# Microcontroller.net
KiCad netlist of a schematic drawn in Altium Designer
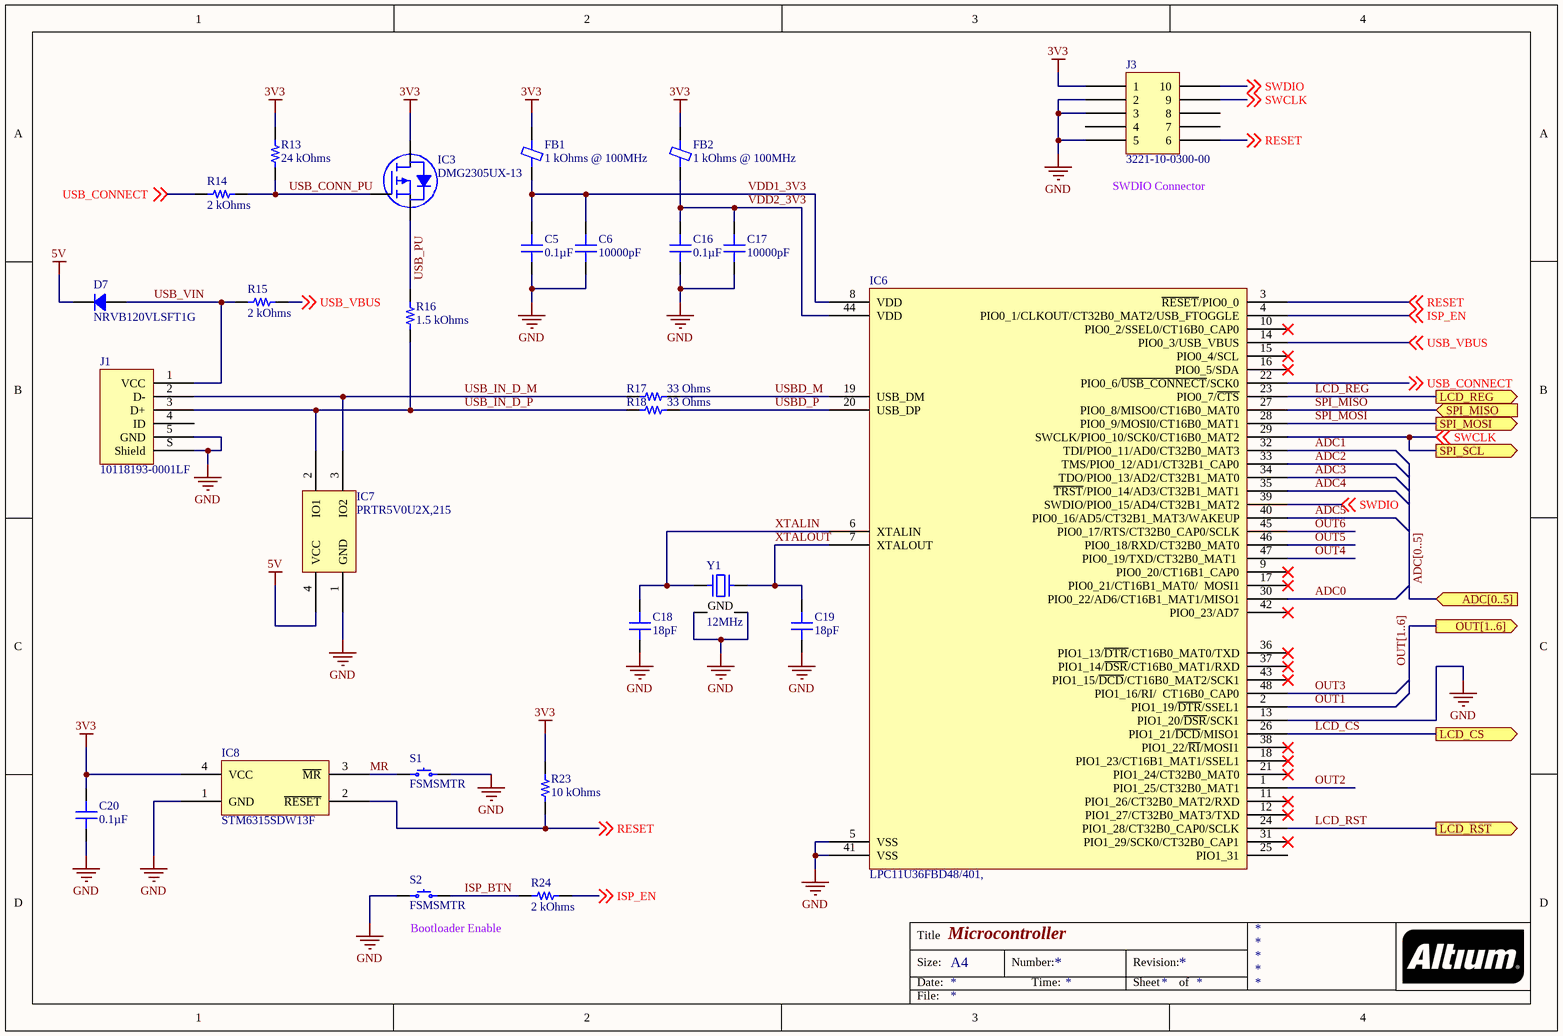
[diagram p0: Microcontroller.SchDoc]

(export (version "E")
  (design (tool "Eeschema 10.0.6"))
  (components
    (comp (ref "C5")
      (value "0.1µF")
      (footprint "CAP 0603_1608")
      (description "CAP CER 0.1UF 16V X7R 0603")
      (fields (field (name "PART NUMBER") "CS0603KRX7R7BB104") (field (name "MANUFACTURER") "Yageo"))
      (libsource (lib "Celestial Altium Library - altium_library") (part "Capacitor"))
    )
    (comp (ref "C6")
      (value "10000pF")
      (footprint "CAP 0603_1608")
      (description "CAP CER 10000PF 50V X7R 0603")
      (fields (field (name "PART NUMBER") "AC0603KPX7R9BB103") (field (name "MANUFACTURER") "Yageo"))
      (libsource (lib "Celestial Altium Library - altium_library") (part "Capacitor"))
    )
    (comp (ref "C16")
      (value "0.1µF")
      (footprint "CAP 0603_1608")
      (description "CAP CER 0.1UF 16V X7R 0603")
      (fields (field (name "PART NUMBER") "CS0603KRX7R7BB104") (field (name "MANUFACTURER") "Yageo"))
      (libsource (lib "Celestial Altium Library - altium_library") (part "Capacitor"))
    )
    (comp (ref "C17")
      (value "10000pF")
      (footprint "CAP 0603_1608")
      (description "CAP CER 10000PF 50V X7R 0603")
      (fields (field (name "PART NUMBER") "AC0603KPX7R9BB103") (field (name "MANUFACTURER") "Yageo"))
      (libsource (lib "Celestial Altium Library - altium_library") (part "Capacitor"))
    )
    (comp (ref "C18")
      (value "18pF")
      (footprint "CAP 0603_1608")
      (description "CAP CER 18PF 50V C0G/NP0 0603")
      (fields (field (name "PART NUMBER") "C0603C180K5GACTU") (field (name "MANUFACTURER") "KEMET"))
      (libsource (lib "Celestial Altium Library - altium_library") (part "Capacitor"))
    )
    (comp (ref "C19")
      (value "18pF")
      (footprint "CAP 0603_1608")
      (description "CAP CER 18PF 50V C0G/NP0 0603")
      (fields (field (name "PART NUMBER") "C0603C180K5GACTU") (field (name "MANUFACTURER") "KEMET"))
      (libsource (lib "Celestial Altium Library - altium_library") (part "Capacitor"))
    )
    (comp (ref "C20")
      (value "0.1µF")
      (footprint "CAP 0603_1608")
      (description "CAP CER 0.1UF 16V X7R 0603")
      (fields (field (name "PART NUMBER") "CS0603KRX7R7BB104") (field (name "MANUFACTURER") "Yageo"))
      (libsource (lib "Celestial Altium Library - altium_library") (part "Capacitor"))
    )
    (comp (ref "D7")
      (value "NRVB120VLSFT1G")
      (footprint "SOD123F")
      (description "DIODE SCHOTTKY 20V 1A SOD123")
      (fields (field (name "MANUFACTURER") "ON Semiconductor"))
      (libsource (lib "Celestial Altium Library - altium_library") (part "Diode"))
    )
    (comp (ref "FB1")
      (value "1 kOhms @ 100MHz")
      (footprint "FER 0603_1608")
      (description "FERRITE BEAD,HIGH CURRENT, 0603")
      (fields (field (name "PART NUMBER") "FBTH1608HE102-T") (field (name "MANUFACTURER") "Taiyo Yuden"))
      (libsource (lib "Celestial Altium Library - altium_library") (part "Ferrite Chip"))
    )
    (comp (ref "FB2")
      (value "1 kOhms @ 100MHz")
      (footprint "FER 0603_1608")
      (description "FERRITE BEAD,HIGH CURRENT, 0603")
      (fields (field (name "PART NUMBER") "FBTH1608HE102-T") (field (name "MANUFACTURER") "Taiyo Yuden"))
      (libsource (lib "Celestial Altium Library - altium_library") (part "Ferrite Chip"))
    )
    (comp (ref "IC3")
      (value "DMG2305UX-13")
      (footprint "DIODES SOT-23-3")
      (description "MOSFET P-CH 20V 4.2A SOT23")
      (fields (field (name "MANUFACTURER") "Diodes Incorporated"))
      (libsource (lib "Celestial Altium Library - altium_library") (part "DIODES MOSFET P-CH SOT-23-3"))
    )
    (comp (ref "IC6")
      (value "LPC11U36FBD48/401,")
      (footprint "NXP LQFP-48 7X7MM")
      (description "IC MCU 32BIT 96KB FLASH 48LQFP")
      (fields (field (name "MANUFACTURER") "NXP USA Inc."))
      (libsource (lib "Celestial Altium Library - altium_library") (part "NXP LPC11U3X LQFP48"))
    )
    (comp (ref "IC7")
      (value "PRTR5V0U2X,215")
      (footprint "SOT143B")
      (description "TVS DIODE 5.5V SOT143B")
      (fields (field (name "MANUFACTURER") "Nexperia USA Inc."))
      (libsource (lib "Celestial Altium Library - altium_library") (part "NXP PRTR5V0U2X"))
    )
    (comp (ref "IC8")
      (value "STM6315SDW13F")
      (footprint "ST SOT-143-4")
      (description "IC SUPERVISOR 1 CHANNEL SOT143-4")
      (fields (field (name "MANUFACTURER") "STMicroelectronics"))
      (libsource (lib "Celestial Altium Library - altium_library") (part "ST STM3615"))
    )
    (comp (ref "J1")
      (value "10118193-0001LF")
      (footprint "FCI USB 10118193-0001LF")
      (description "CONN RCPT USB2.0 MICRO B SMD R/A")
      (fields (field (name "MANUFACTURER") "Amphenol ICC (FCI)"))
      (libsource (lib "Celestial Altium Library - altium_library") (part "USB 2.0 Type B Micro"))
    )
    (comp (ref "J3")
      (value "3221-10-0300-00")
      (footprint "CNC TECH 3221-10-0300-00")
      (description "CONN HEADER SMD 10POS 1.27MM")
      (fields (field (name "MANUFACTURER") "CNC Tech"))
      (libsource (lib "Celestial Altium Library - altium_library") (part "2x5 Pin"))
    )
    (comp (ref "R13")
      (value "24 kOhms")
      (footprint "RES 0603_1608")
      (description "RES SMD 24K OHM 1% 1/10W 0603")
      (fields
        (field (name "PART NUMBER") "ERJ-3EKF2402V")
        (field (name "MANUFACTURER") "Panasonic Electronic Components")
      )
      (libsource (lib "Celestial Altium Library - altium_library") (part "Resistor"))
    )
    (comp (ref "R14")
      (value "2 kOhms")
      (footprint "RES 0603_1608")
      (description "RES SMD 2K OHM 1% 1/10W 0603")
      (fields
        (field (name "PART NUMBER") "ERJ-3EKF2001V")
        (field (name "MANUFACTURER") "Panasonic Electronic Components")
      )
      (libsource (lib "Celestial Altium Library - altium_library") (part "Resistor"))
    )
    (comp (ref "R15")
      (value "2 kOhms")
      (footprint "RES 0603_1608")
      (description "RES SMD 2K OHM 5% 1/4W 0603")
      (fields
        (field (name "PART NUMBER") "ERJ-PA3J202V")
        (field (name "MANUFACTURER") "Panasonic Electronic Components")
      )
      (libsource (lib "Celestial Altium Library - altium_library") (part "Resistor"))
    )
    (comp (ref "R16")
      (value "1.5 kOhms")
      (footprint "RES 0603_1608")
      (description "RES SMD 1.5K OHM 1% 1/10W 0603")
      (fields
        (field (name "PART NUMBER") "ERJ-3EKF1501V")
        (field (name "MANUFACTURER") "Panasonic Electronic Components")
      )
      (libsource (lib "Celestial Altium Library - altium_library") (part "Resistor"))
    )
    (comp (ref "R17")
      (value "33 Ohms")
      (footprint "RES 0603_1608")
      (description "RES SMD 33 OHM 1% 1/10W 0603")
      (fields
        (field (name "PART NUMBER") "ERJ-3EKF33R0V")
        (field (name "MANUFACTURER") "Panasonic Electronic Components")
      )
      (libsource (lib "Celestial Altium Library - altium_library") (part "Resistor"))
    )
    (comp (ref "R18")
      (value "33 Ohms")
      (footprint "RES 0603_1608")
      (description "RES SMD 33 OHM 1% 1/10W 0603")
      (fields
        (field (name "PART NUMBER") "ERJ-3EKF33R0V")
        (field (name "MANUFACTURER") "Panasonic Electronic Components")
      )
      (libsource (lib "Celestial Altium Library - altium_library") (part "Resistor"))
    )
    (comp (ref "R23")
      (value "10 kOhms")
      (footprint "RES 0603_1608")
      (description "RES SMD 10K OHM 1% 1/10W 0603")
      (fields
        (field (name "PART NUMBER") "ERJ-3EKF1002V")
        (field (name "MANUFACTURER") "Panasonic Electronic Components")
      )
      (libsource (lib "Celestial Altium Library - altium_library") (part "Resistor"))
    )
    (comp (ref "R24")
      (value "2 kOhms")
      (footprint "RES 0603_1608")
      (description "RES SMD 2K OHM 5% 1/4W 0603")
      (fields
        (field (name "PART NUMBER") "ERJ-PA3J202V")
        (field (name "MANUFACTURER") "Panasonic Electronic Components")
      )
      (libsource (lib "Celestial Altium Library - altium_library") (part "Resistor"))
    )
    (comp (ref "S1")
      (value "FSMSMTR")
      (footprint "TE FSMSMTR")
      (description "SWITCH TACTILE SPST-NO 0.05A 24V")
      (fields (field (name "MANUFACTURER") "TE Connectivity ALCOSWITCH Switches"))
      (libsource (lib "Celestial Altium Library - altium_library") (part "SPST-NO 2 PIN"))
    )
    (comp (ref "S2")
      (value "FSMSMTR")
      (footprint "TE FSMSMTR")
      (description "SWITCH TACTILE SPST-NO 0.05A 24V")
      (fields (field (name "MANUFACTURER") "TE Connectivity ALCOSWITCH Switches"))
      (libsource (lib "Celestial Altium Library - altium_library") (part "SPST-NO 2 PIN"))
    )
    (comp (ref "Y1")
      (value "12MHz")
      (footprint "ABRACON ABM8G")
      (description "IOT 12MHZ 10PF XTAL")
      (fields
        (field (name "PART NUMBER") "ABM8G-106-12.000MHZ-T")
        (field (name "MANUFACTURER") "Abracon LLC")
      )
      (libsource (lib "Celestial Altium Library - altium_library") (part "Abracon Crystal ABM8G"))
    )
  )
  (nets
    (net (code "1") (name "/ADC0") (class "Default")
      (node (ref "IC6") (pin "30") (pinfunction "PIO0_22/AD6/CT16B1_MAT1/MISO1_30") (pintype "passive"))
    )
    (net (code "2") (name "/ADC1") (class "Default")
      (node (ref "IC6") (pin "32") (pinfunction "TDI/PIO0_11/AD0/CT32B0_MAT3_32") (pintype "passive"))
    )
    (net (code "3") (name "/ADC2") (class "Default")
      (node (ref "IC6") (pin "33") (pinfunction "TMS/PIO0_12/AD1/CT32B1_CAP0_33") (pintype "passive"))
    )
    (net (code "4") (name "/ADC3") (class "Default")
      (node (ref "IC6") (pin "34") (pinfunction "TDO/PIO0_13/AD2/CT32B1_MAT0_34") (pintype "passive"))
    )
    (net (code "5") (name "/ADC4") (class "Default")
      (node (ref "IC6") (pin "35") (pinfunction "~{TRST}/PIO0_14/AD3/CT32B1_MAT1_35") (pintype "passive"))
    )
    (net (code "6") (name "/ADC5") (class "Default")
      (node (ref "IC6") (pin "40") (pinfunction "PIO0_16/AD5/CT32B1_MAT3/WAKEUP_40") (pintype "passive"))
    )
    (net (code "8") (name "/ISP_BTN") (class "Default")
      (node (ref "R24") (pin "1") (pinfunction "1_1") (pintype "passive"))
      (node (ref "S2") (pin "2") (pinfunction "2_2") (pintype "passive"))
    )
    (net (code "9") (name "/LCD_CS") (class "Default")
      (node (ref "IC6") (pin "26") (pinfunction "PIO1_21/~{DCD}/MISO1_26") (pintype "passive"))
    )
    (net (code "10") (name "/LCD_REG") (class "Default")
      (node (ref "IC6") (pin "23") (pinfunction "PIO0_7/~{CTS}_23") (pintype "passive"))
    )
    (net (code "11") (name "/LCD_RST") (class "Default")
      (node (ref "IC6") (pin "24") (pinfunction "PIO1_28/CT32B0_CAP0/SCLK_24") (pintype "passive"))
    )
    (net (code "12") (name "/MR") (class "Default")
      (node (ref "IC8") (pin "3") (pinfunction "~{MR}_3") (pintype "passive"))
      (node (ref "S1") (pin "1") (pinfunction "1_1") (pintype "passive"))
    )
    (net (code "13") (name "/OUT1") (class "Default")
      (node (ref "IC6") (pin "2") (pinfunction "PIO1_19/~{DTR}/SSEL1_2") (pintype "passive"))
    )
    (net (code "14") (name "/OUT2") (class "Default")
      (node (ref "IC6") (pin "1") (pinfunction "PIO1_25/CT32B0_MAT1_1") (pintype "passive"))
    )
    (net (code "15") (name "/OUT3") (class "Default")
      (node (ref "IC6") (pin "48") (pinfunction "PIO1_16/RI/__CT16B0_CAP0_48") (pintype "passive"))
    )
    (net (code "16") (name "/OUT4") (class "Default")
      (node (ref "IC6") (pin "47") (pinfunction "PIO0_19/TXD/CT32B0_MAT1_47") (pintype "passive"))
    )
    (net (code "17") (name "/OUT5") (class "Default")
      (node (ref "IC6") (pin "46") (pinfunction "PIO0_18/RXD/CT32B0_MAT0_46") (pintype "passive"))
    )
    (net (code "18") (name "/OUT6") (class "Default")
      (node (ref "IC6") (pin "45") (pinfunction "PIO0_17/RTS/CT32B0_CAP0/SCLK_45") (pintype "passive"))
    )
    (net (code "20") (name "/SPI_MISO") (class "Default")
      (node (ref "IC6") (pin "27") (pinfunction "PIO0_8/MISO0/CT16B0_MAT0_27") (pintype "passive"))
    )
    (net (code "21") (name "/SPI_MOSI") (class "Default")
      (node (ref "IC6") (pin "28") (pinfunction "PIO0_9/MOSI0/CT16B0_MAT1_28") (pintype "passive"))
    )
    (net (code "22") (name "/USBD_M") (class "Default")
      (node (ref "IC6") (pin "19") (pinfunction "USB_DM_19") (pintype "passive"))
      (node (ref "R17") (pin "2") (pinfunction "2_2") (pintype "passive"))
    )
    (net (code "23") (name "/USBD_P") (class "Default")
      (node (ref "IC6") (pin "20") (pinfunction "USB_DP_20") (pintype "passive"))
      (node (ref "R18") (pin "2") (pinfunction "2_2") (pintype "passive"))
    )
    (net (code "24") (name "/USB_CONN_PU") (class "Default")
      (node (ref "IC3") (pin "1") (pinfunction "G_1") (pintype "passive"))
      (node (ref "R13") (pin "1") (pinfunction "1_1") (pintype "passive"))
      (node (ref "R14") (pin "2") (pinfunction "2_2") (pintype "passive"))
    )
    (net (code "25") (name "/USB_IN_D_M") (class "Default")
      (node (ref "IC7") (pin "3") (pinfunction "IO2_3") (pintype "passive"))
      (node (ref "J1") (pin "2") (pinfunction "D-_2") (pintype "passive"))
      (node (ref "R17") (pin "1") (pinfunction "1_1") (pintype "passive"))
    )
    (net (code "26") (name "/USB_IN_D_P") (class "Default")
      (node (ref "IC7") (pin "2") (pinfunction "IO1_2") (pintype "passive"))
      (node (ref "J1") (pin "3") (pinfunction "D+_3") (pintype "passive"))
      (node (ref "R16") (pin "1") (pinfunction "1_1") (pintype "passive"))
      (node (ref "R18") (pin "1") (pinfunction "1_1") (pintype "passive"))
    )
    (net (code "27") (name "/USB_PU") (class "Default")
      (node (ref "IC3") (pin "2") (pinfunction "S_2") (pintype "passive"))
      (node (ref "R16") (pin "2") (pinfunction "2_2") (pintype "passive"))
    )
    (net (code "28") (name "/USB_VIN") (class "Default")
      (node (ref "D7") (pin "1") (pinfunction "1_1") (pintype "passive"))
      (node (ref "J1") (pin "1") (pinfunction "VCC_1") (pintype "passive"))
      (node (ref "R15") (pin "1") (pinfunction "1_1") (pintype "passive"))
    )
    (net (code "29") (name "/VDD1_3V3") (class "Default")
      (node (ref "C5") (pin "2") (pinfunction "2_2") (pintype "passive"))
      (node (ref "C6") (pin "2") (pinfunction "2_2") (pintype "passive"))
      (node (ref "FB1") (pin "1") (pinfunction "1_1") (pintype "passive"))
      (node (ref "IC6") (pin "8") (pinfunction "VDD_8") (pintype "passive"))
    )
    (net (code "30") (name "/VDD2_3V3") (class "Default")
      (node (ref "C16") (pin "2") (pinfunction "2_2") (pintype "passive"))
      (node (ref "C17") (pin "2") (pinfunction "2_2") (pintype "passive"))
      (node (ref "FB2") (pin "1") (pinfunction "1_1") (pintype "passive"))
      (node (ref "IC6") (pin "44") (pinfunction "VDD_44") (pintype "passive"))
    )
    (net (code "31") (name "/XTALIN") (class "Default")
      (node (ref "C18") (pin "2") (pinfunction "2_2") (pintype "passive"))
      (node (ref "IC6") (pin "6") (pinfunction "XTALIN_6") (pintype "passive"))
      (node (ref "Y1") (pin "1") (pinfunction "1_1") (pintype "passive"))
    )
    (net (code "32") (name "/XTALOUT") (class "Default")
      (node (ref "C19") (pin "2") (pinfunction "2_2") (pintype "passive"))
      (node (ref "IC6") (pin "7") (pinfunction "XTALOUT_7") (pintype "passive"))
      (node (ref "Y1") (pin "3") (pinfunction "3_3") (pintype "passive"))
    )
    (net (code "33") (name "3V3") (class "Default")
      (node (ref "C20") (pin "2") (pinfunction "2_2") (pintype "passive"))
      (node (ref "FB1") (pin "2") (pinfunction "2_2") (pintype "passive"))
      (node (ref "FB2") (pin "2") (pinfunction "2_2") (pintype "passive"))
      (node (ref "IC3") (pin "3") (pinfunction "D_3") (pintype "passive"))
      (node (ref "IC8") (pin "4") (pinfunction "VCC_4") (pintype "passive"))
      (node (ref "J3") (pin "1") (pinfunction "1_1") (pintype "passive"))
      (node (ref "R13") (pin "2") (pinfunction "2_2") (pintype "passive"))
      (node (ref "R23") (pin "2") (pinfunction "2_2") (pintype "passive"))
    )
    (net (code "34") (name "5V") (class "Default")
      (node (ref "D7") (pin "2") (pinfunction "2_2") (pintype "passive"))
      (node (ref "IC7") (pin "4") (pinfunction "VCC_4") (pintype "passive"))
    )
    (net (code "35") (name "GND") (class "Default")
      (node (ref "C16") (pin "1") (pinfunction "1_1") (pintype "passive"))
      (node (ref "C17") (pin "1") (pinfunction "1_1") (pintype "passive"))
      (node (ref "C18") (pin "1") (pinfunction "1_1") (pintype "passive"))
      (node (ref "C19") (pin "1") (pinfunction "1_1") (pintype "passive"))
      (node (ref "C20") (pin "1") (pinfunction "1_1") (pintype "passive"))
      (node (ref "C5") (pin "1") (pinfunction "1_1") (pintype "passive"))
      (node (ref "C6") (pin "1") (pinfunction "1_1") (pintype "passive"))
      (node (ref "IC6") (pin "13") (pinfunction "PIO1_20/~{DSR}/SCK1_13") (pintype "passive"))
      (node (ref "IC6") (pin "41") (pinfunction "VSS_41") (pintype "passive"))
      (node (ref "IC6") (pin "5") (pinfunction "VSS_5") (pintype "passive"))
      (node (ref "IC7") (pin "1") (pinfunction "GND_1") (pintype "passive"))
      (node (ref "IC8") (pin "1") (pinfunction "GND_1") (pintype "passive"))
      (node (ref "J1") (pin "5") (pinfunction "GND_5") (pintype "passive"))
      (node (ref "J1") (pin "S") (pinfunction "Shield_S") (pintype "passive"))
      (node (ref "J3") (pin "2") (pinfunction "2_2") (pintype "passive"))
      (node (ref "J3") (pin "3") (pinfunction "3_3") (pintype "passive"))
      (node (ref "J3") (pin "5") (pinfunction "5_5") (pintype "passive"))
      (node (ref "S1") (pin "2") (pinfunction "2_2") (pintype "passive"))
      (node (ref "S2") (pin "1") (pinfunction "1_1") (pintype "passive"))
      (node (ref "Y1") (pin "2") (pinfunction "GND_2") (pintype "passive"))
      (node (ref "Y1") (pin "4") (pinfunction "GND_4") (pintype "passive"))
    )
    (net (code "36") (name "ISP_EN") (class "Default")
      (node (ref "IC6") (pin "4") (pinfunction "PIO0_1/CLKOUT/CT32B0_MAT2/USB_FTOGGLE_4") (pintype "passive"))
      (node (ref "R24") (pin "2") (pinfunction "2_2") (pintype "passive"))
    )
    (net (code "37") (name "RESET") (class "Default")
      (node (ref "IC6") (pin "3") (pinfunction "~{RESET}/PIO0_0_3") (pintype "passive"))
      (node (ref "IC8") (pin "2") (pinfunction "~{RESET}_2") (pintype "passive"))
      (node (ref "J3") (pin "6") (pinfunction "6_6") (pintype "passive"))
      (node (ref "R23") (pin "1") (pinfunction "1_1") (pintype "passive"))
    )
    (net (code "38") (name "SWCLK") (class "Default")
      (node (ref "IC6") (pin "29") (pinfunction "SWCLK/PIO0_10/SCK0/CT16B0_MAT2_29") (pintype "passive"))
      (node (ref "J3") (pin "9") (pinfunction "9_9") (pintype "passive"))
    )
    (net (code "39") (name "SWDIO") (class "Default")
      (node (ref "IC6") (pin "39") (pinfunction "SWDIO/PIO0_15/AD4/CT32B1_MAT2_39") (pintype "passive"))
      (node (ref "J3") (pin "10") (pinfunction "10_10") (pintype "passive"))
    )
    (net (code "40") (name "USB_CONNECT") (class "Default")
      (node (ref "IC6") (pin "22") (pinfunction "PIO0_6/~{USB_CONNECT}/SCK0_22") (pintype "passive"))
      (node (ref "R14") (pin "1") (pinfunction "1_1") (pintype "passive"))
    )
    (net (code "41") (name "USB_VBUS") (class "Default")
      (node (ref "IC6") (pin "14") (pinfunction "PIO0_3/USB_VBUS_14") (pintype "passive"))
      (node (ref "R15") (pin "2") (pinfunction "2_2") (pintype "passive"))
    )
    (net (code "42") (name "unconnected-(IC6-PIO0_2{slash}SSEL0{slash}CT16B0_CAP0-Pad10)") (class "Default")
      (node (ref "IC6") (pin "10") (pinfunction "PIO0_2/SSEL0/CT16B0_CAP0_10") (pintype "passive+no_connect"))
    )
    (net (code "43") (name "unconnected-(IC6-PIO0_4{slash}SCL-Pad15)") (class "Default")
      (node (ref "IC6") (pin "15") (pinfunction "PIO0_4/SCL_15") (pintype "passive+no_connect"))
    )
    (net (code "44") (name "unconnected-(IC6-PIO0_5{slash}SDA-Pad16)") (class "Default")
      (node (ref "IC6") (pin "16") (pinfunction "PIO0_5/SDA_16") (pintype "passive+no_connect"))
    )
    (net (code "45") (name "unconnected-(IC6-PIO0_20{slash}CT16B1_CAP0-Pad9)") (class "Default")
      (node (ref "IC6") (pin "9") (pinfunction "PIO0_20/CT16B1_CAP0_9") (pintype "passive+no_connect"))
    )
    (net (code "46") (name "unconnected-(IC6-PIO0_21{slash}CT16B1_MAT0{slash}__MOSI1-Pad17)") (class "Default")
      (node (ref "IC6") (pin "17") (pinfunction "PIO0_21/CT16B1_MAT0/__MOSI1_17") (pintype "passive+no_connect"))
    )
    (net (code "47") (name "unconnected-(IC6-PIO0_23{slash}AD7-Pad42)") (class "Default")
      (node (ref "IC6") (pin "42") (pinfunction "PIO0_23/AD7_42") (pintype "passive+no_connect"))
    )
    (net (code "48") (name "unconnected-(IC6-PIO1_13{slash}~{DTR}{slash}CT16B0_MAT0{slash}TXD-Pad36)") (class "Default")
      (node (ref "IC6") (pin "36") (pinfunction "PIO1_13/~{DTR}/CT16B0_MAT0/TXD_36") (pintype "passive+no_connect"))
    )
    (net (code "49") (name "unconnected-(IC6-PIO1_14{slash}~{DSR}{slash}CT16B0_MAT1{slash}RXD-Pad37)") (class "Default")
      (node (ref "IC6") (pin "37") (pinfunction "PIO1_14/~{DSR}/CT16B0_MAT1/RXD_37") (pintype "passive+no_connect"))
    )
    (net (code "50") (name "unconnected-(IC6-PIO1_15{slash}~{DCD}{slash}CT16B0_MAT2{slash}SCK1-Pad43)") (class "Default")
      (node (ref "IC6") (pin "43") (pinfunction "PIO1_15/~{DCD}/CT16B0_MAT2/SCK1_43") (pintype "passive+no_connect"))
    )
    (net (code "51") (name "unconnected-(IC6-PIO1_22{slash}~{RI}{slash}MOSI1-Pad38)") (class "Default")
      (node (ref "IC6") (pin "38") (pinfunction "PIO1_22/~{RI}/MOSI1_38") (pintype "passive+no_connect"))
    )
    (net (code "52") (name "unconnected-(IC6-PIO1_23{slash}CT16B1_MAT1{slash}SSEL1-Pad18)") (class "Default")
      (node (ref "IC6") (pin "18") (pinfunction "PIO1_23/CT16B1_MAT1/SSEL1_18") (pintype "passive+no_connect"))
    )
    (net (code "53") (name "unconnected-(IC6-PIO1_24{slash}CT32B0_MAT0-Pad21)") (class "Default")
      (node (ref "IC6") (pin "21") (pinfunction "PIO1_24/CT32B0_MAT0_21") (pintype "passive+no_connect"))
    )
    (net (code "54") (name "unconnected-(IC6-PIO1_26{slash}CT32B0_MAT2{slash}RXD-Pad11)") (class "Default")
      (node (ref "IC6") (pin "11") (pinfunction "PIO1_26/CT32B0_MAT2/RXD_11") (pintype "passive+no_connect"))
    )
    (net (code "55") (name "unconnected-(IC6-PIO1_27{slash}CT32B0_MAT3{slash}TXD-Pad12)") (class "Default")
      (node (ref "IC6") (pin "12") (pinfunction "PIO1_27/CT32B0_MAT3/TXD_12") (pintype "passive+no_connect"))
    )
    (net (code "56") (name "unconnected-(IC6-PIO1_29{slash}SCK0{slash}CT32B0_CAP1-Pad31)") (class "Default")
      (node (ref "IC6") (pin "31") (pinfunction "PIO1_29/SCK0/CT32B0_CAP1_31") (pintype "passive+no_connect"))
    )
    (net (code "57") (name "unconnected-(IC6-PIO1_31-Pad25)") (class "Default")
      (node (ref "IC6") (pin "25") (pinfunction "PIO1_31_25") (pintype "passive"))
    )
    (net (code "58") (name "unconnected-(J1-ID-Pad4)") (class "Default")
      (node (ref "J1") (pin "4") (pinfunction "ID_4") (pintype "passive"))
    )
    (net (code "59") (name "unconnected-(J3-Pad4)") (class "Default")
      (node (ref "J3") (pin "4") (pinfunction "4_4") (pintype "passive"))
    )
    (net (code "60") (name "unconnected-(J3-Pad7)") (class "Default")
      (node (ref "J3") (pin "7") (pinfunction "7_7") (pintype "passive"))
    )
    (net (code "61") (name "unconnected-(J3-Pad8)") (class "Default")
      (node (ref "J3") (pin "8") (pinfunction "8_8") (pintype "passive"))
    )
  )
)
